# Micro.net
KiCad netlist of a schematic drawn in Altium Designer
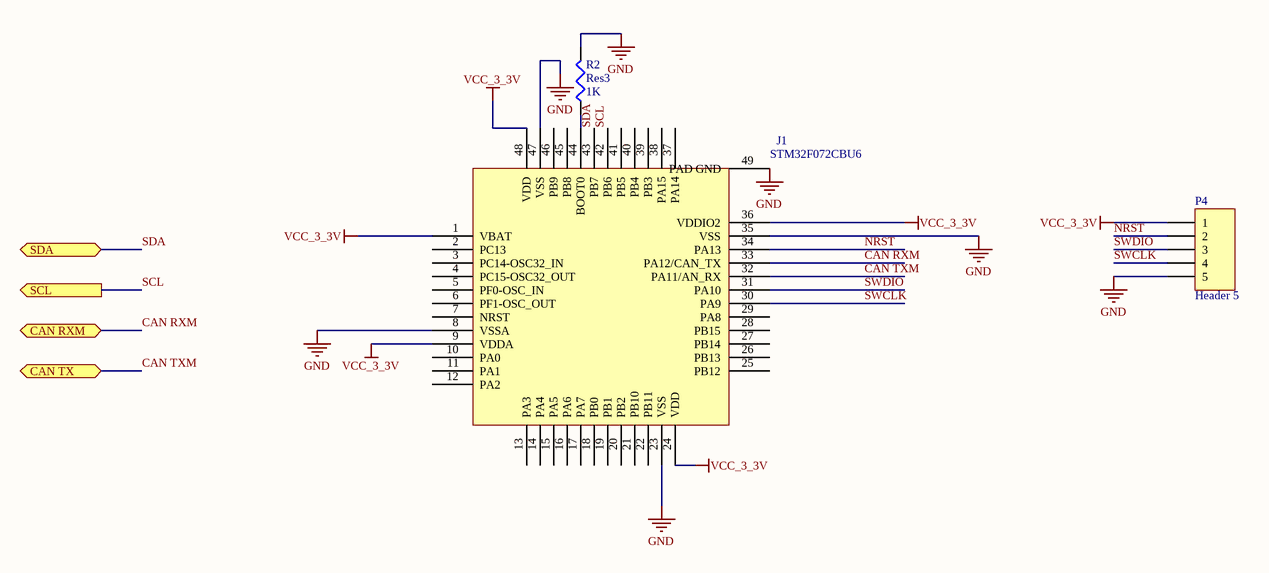
[diagram p0: Micro.SchDoc]

(export (version "E")
  (design (tool "Eeschema 10.0.6"))
  (components
    (comp (ref "J1")
      (value "STM32F072CBU6")
      (footprint "STM32F072CBU6 - duplicate")
      (description "MICROCONTROLLER")
      (libsource (lib "CAN_Node") (part "STM32F072CBU6"))
    )
    (comp (ref "P4")
      (value "Header 5")
      (footprint "HDR1X5")
      (description "Header, 5-Pin")
      (fields (field (name "PUBLISHER") "Altium Limited"))
      (libsource (lib "Miscellaneous Connectors") (part "Header 5"))
    )
    (comp (ref "R2")
      (value "Res3")
      (footprint "R0805")
      (description "Resistor")
      (fields (field (name "ALTIUM_VALUE") "1K") (field (name "PUBLISHER") "Altium Limited"))
      (libsource (lib "Miscellaneous Devices") (part "Res3"))
    )
  )
  (nets
    (net (code "1") (name "/CAN RXM") (class "Default")
      (node (ref "J1") (pin "33") (pinfunction "PA12/CAN_TX_33") (pintype "passive"))
    )
    (net (code "2") (name "/CAN TXM") (class "Default")
      (node (ref "J1") (pin "32") (pinfunction "PA11/AN_RX_32") (pintype "passive"))
    )
    (net (code "3") (name "/NRST") (class "Default")
      (node (ref "J1") (pin "34") (pinfunction "PA13_34") (pintype "passive"))
      (node (ref "P4") (pin "2") (pinfunction "2_2") (pintype "passive"))
    )
    (net (code "4") (name "/SCL") (class "Default")
      (node (ref "J1") (pin "42") (pinfunction "PB6_42") (pintype "passive"))
    )
    (net (code "5") (name "/SDA") (class "Default")
      (node (ref "J1") (pin "43") (pinfunction "PB7_43") (pintype "passive"))
    )
    (net (code "6") (name "/SWCLK") (class "Default")
      (node (ref "J1") (pin "30") (pinfunction "PA9_30") (pintype "passive"))
      (node (ref "P4") (pin "4") (pinfunction "4_4") (pintype "passive"))
    )
    (net (code "7") (name "/SWDIO") (class "Default")
      (node (ref "J1") (pin "31") (pinfunction "PA10_31") (pintype "passive"))
      (node (ref "P4") (pin "3") (pinfunction "3_3") (pintype "passive"))
    )
    (net (code "8") (name "GND") (class "Default")
      (node (ref "J1") (pin "23") (pinfunction "VSS_23") (pintype "passive"))
      (node (ref "J1") (pin "35") (pinfunction "VSS_35") (pintype "passive"))
      (node (ref "J1") (pin "47") (pinfunction "VSS_47") (pintype "passive"))
      (node (ref "J1") (pin "49") (pinfunction "PAD_GND_49") (pintype "passive"))
      (node (ref "J1") (pin "8") (pinfunction "VSSA_8") (pintype "passive"))
      (node (ref "P4") (pin "5") (pinfunction "5_5") (pintype "passive"))
      (node (ref "R2") (pin "2") (pinfunction "2_2") (pintype "passive"))
    )
    (net (code "9") (name "Net-(J1-BOOT0)") (class "Default")
      (node (ref "J1") (pin "44") (pinfunction "BOOT0_44") (pintype "passive"))
      (node (ref "R2") (pin "1") (pinfunction "1_1") (pintype "passive"))
    )
    (net (code "10") (name "VCC_3_3V") (class "Default")
      (node (ref "J1") (pin "1") (pinfunction "VBAT_1") (pintype "passive"))
      (node (ref "J1") (pin "24") (pinfunction "VDD_24") (pintype "passive"))
      (node (ref "J1") (pin "36") (pinfunction "VDDIO2_36") (pintype "passive"))
      (node (ref "J1") (pin "48") (pinfunction "VDD_48") (pintype "passive"))
      (node (ref "J1") (pin "9") (pinfunction "VDDA_9") (pintype "passive"))
      (node (ref "P4") (pin "1") (pinfunction "1_1") (pintype "passive"))
    )
    (net (code "11") (name "unconnected-(J1-NRST-Pad7)") (class "Default")
      (node (ref "J1") (pin "7") (pinfunction "NRST_7") (pintype "passive"))
    )
    (net (code "12") (name "unconnected-(J1-PA0-Pad10)") (class "Default")
      (node (ref "J1") (pin "10") (pinfunction "PA0_10") (pintype "passive"))
    )
    (net (code "13") (name "unconnected-(J1-PA1-Pad11)") (class "Default")
      (node (ref "J1") (pin "11") (pinfunction "PA1_11") (pintype "passive"))
    )
    (net (code "14") (name "unconnected-(J1-PA2-Pad12)") (class "Default")
      (node (ref "J1") (pin "12") (pinfunction "PA2_12") (pintype "passive"))
    )
    (net (code "15") (name "unconnected-(J1-PA3-Pad13)") (class "Default")
      (node (ref "J1") (pin "13") (pinfunction "PA3_13") (pintype "passive"))
    )
    (net (code "16") (name "unconnected-(J1-PA4-Pad14)") (class "Default")
      (node (ref "J1") (pin "14") (pinfunction "PA4_14") (pintype "passive"))
    )
    (net (code "17") (name "unconnected-(J1-PA5-Pad15)") (class "Default")
      (node (ref "J1") (pin "15") (pinfunction "PA5_15") (pintype "passive"))
    )
    (net (code "18") (name "unconnected-(J1-PA6-Pad16)") (class "Default")
      (node (ref "J1") (pin "16") (pinfunction "PA6_16") (pintype "passive"))
    )
    (net (code "19") (name "unconnected-(J1-PA7-Pad17)") (class "Default")
      (node (ref "J1") (pin "17") (pinfunction "PA7_17") (pintype "passive"))
    )
    (net (code "20") (name "unconnected-(J1-PA8-Pad29)") (class "Default")
      (node (ref "J1") (pin "29") (pinfunction "PA8_29") (pintype "passive"))
    )
    (net (code "21") (name "unconnected-(J1-PA14-Pad37)") (class "Default")
      (node (ref "J1") (pin "37") (pinfunction "PA14_37") (pintype "passive"))
    )
    (net (code "22") (name "unconnected-(J1-PA15-Pad38)") (class "Default")
      (node (ref "J1") (pin "38") (pinfunction "PA15_38") (pintype "passive"))
    )
    (net (code "23") (name "unconnected-(J1-PB0-Pad18)") (class "Default")
      (node (ref "J1") (pin "18") (pinfunction "PB0_18") (pintype "passive"))
    )
    (net (code "24") (name "unconnected-(J1-PB1-Pad19)") (class "Default")
      (node (ref "J1") (pin "19") (pinfunction "PB1_19") (pintype "passive"))
    )
    (net (code "25") (name "unconnected-(J1-PB2-Pad20)") (class "Default")
      (node (ref "J1") (pin "20") (pinfunction "PB2_20") (pintype "passive"))
    )
    (net (code "26") (name "unconnected-(J1-PB3-Pad39)") (class "Default")
      (node (ref "J1") (pin "39") (pinfunction "PB3_39") (pintype "passive"))
    )
    (net (code "27") (name "unconnected-(J1-PB4-Pad40)") (class "Default")
      (node (ref "J1") (pin "40") (pinfunction "PB4_40") (pintype "passive"))
    )
    (net (code "28") (name "unconnected-(J1-PB5-Pad41)") (class "Default")
      (node (ref "J1") (pin "41") (pinfunction "PB5_41") (pintype "passive"))
    )
    (net (code "29") (name "unconnected-(J1-PB8-Pad45)") (class "Default")
      (node (ref "J1") (pin "45") (pinfunction "PB8_45") (pintype "passive"))
    )
    (net (code "30") (name "unconnected-(J1-PB9-Pad46)") (class "Default")
      (node (ref "J1") (pin "46") (pinfunction "PB9_46") (pintype "passive"))
    )
    (net (code "31") (name "unconnected-(J1-PB10-Pad21)") (class "Default")
      (node (ref "J1") (pin "21") (pinfunction "PB10_21") (pintype "passive"))
    )
    (net (code "32") (name "unconnected-(J1-PB11-Pad22)") (class "Default")
      (node (ref "J1") (pin "22") (pinfunction "PB11_22") (pintype "passive"))
    )
    (net (code "33") (name "unconnected-(J1-PB12-Pad25)") (class "Default")
      (node (ref "J1") (pin "25") (pinfunction "PB12_25") (pintype "passive"))
    )
    (net (code "34") (name "unconnected-(J1-PB13-Pad26)") (class "Default")
      (node (ref "J1") (pin "26") (pinfunction "PB13_26") (pintype "passive"))
    )
    (net (code "35") (name "unconnected-(J1-PB14-Pad27)") (class "Default")
      (node (ref "J1") (pin "27") (pinfunction "PB14_27") (pintype "passive"))
    )
    (net (code "36") (name "unconnected-(J1-PB15-Pad28)") (class "Default")
      (node (ref "J1") (pin "28") (pinfunction "PB15_28") (pintype "passive"))
    )
    (net (code "37") (name "unconnected-(J1-PC13-Pad2)") (class "Default")
      (node (ref "J1") (pin "2") (pinfunction "PC13_2") (pintype "passive"))
    )
    (net (code "38") (name "unconnected-(J1-PC14-OSC32_IN-Pad3)") (class "Default")
      (node (ref "J1") (pin "3") (pinfunction "PC14-OSC32_IN_3") (pintype "passive"))
    )
    (net (code "39") (name "unconnected-(J1-PC15-OSC32_OUT-Pad4)") (class "Default")
      (node (ref "J1") (pin "4") (pinfunction "PC15-OSC32_OUT_4") (pintype "passive"))
    )
    (net (code "40") (name "unconnected-(J1-PF0-OSC_IN-Pad5)") (class "Default")
      (node (ref "J1") (pin "5") (pinfunction "PF0-OSC_IN_5") (pintype "passive"))
    )
    (net (code "41") (name "unconnected-(J1-PF1-OSC_OUT-Pad6)") (class "Default")
      (node (ref "J1") (pin "6") (pinfunction "PF1-OSC_OUT_6") (pintype "passive"))
    )
  )
)
